# OBDII-Ist.net
KiCad netlist of a schematic drawn in Altium Designer
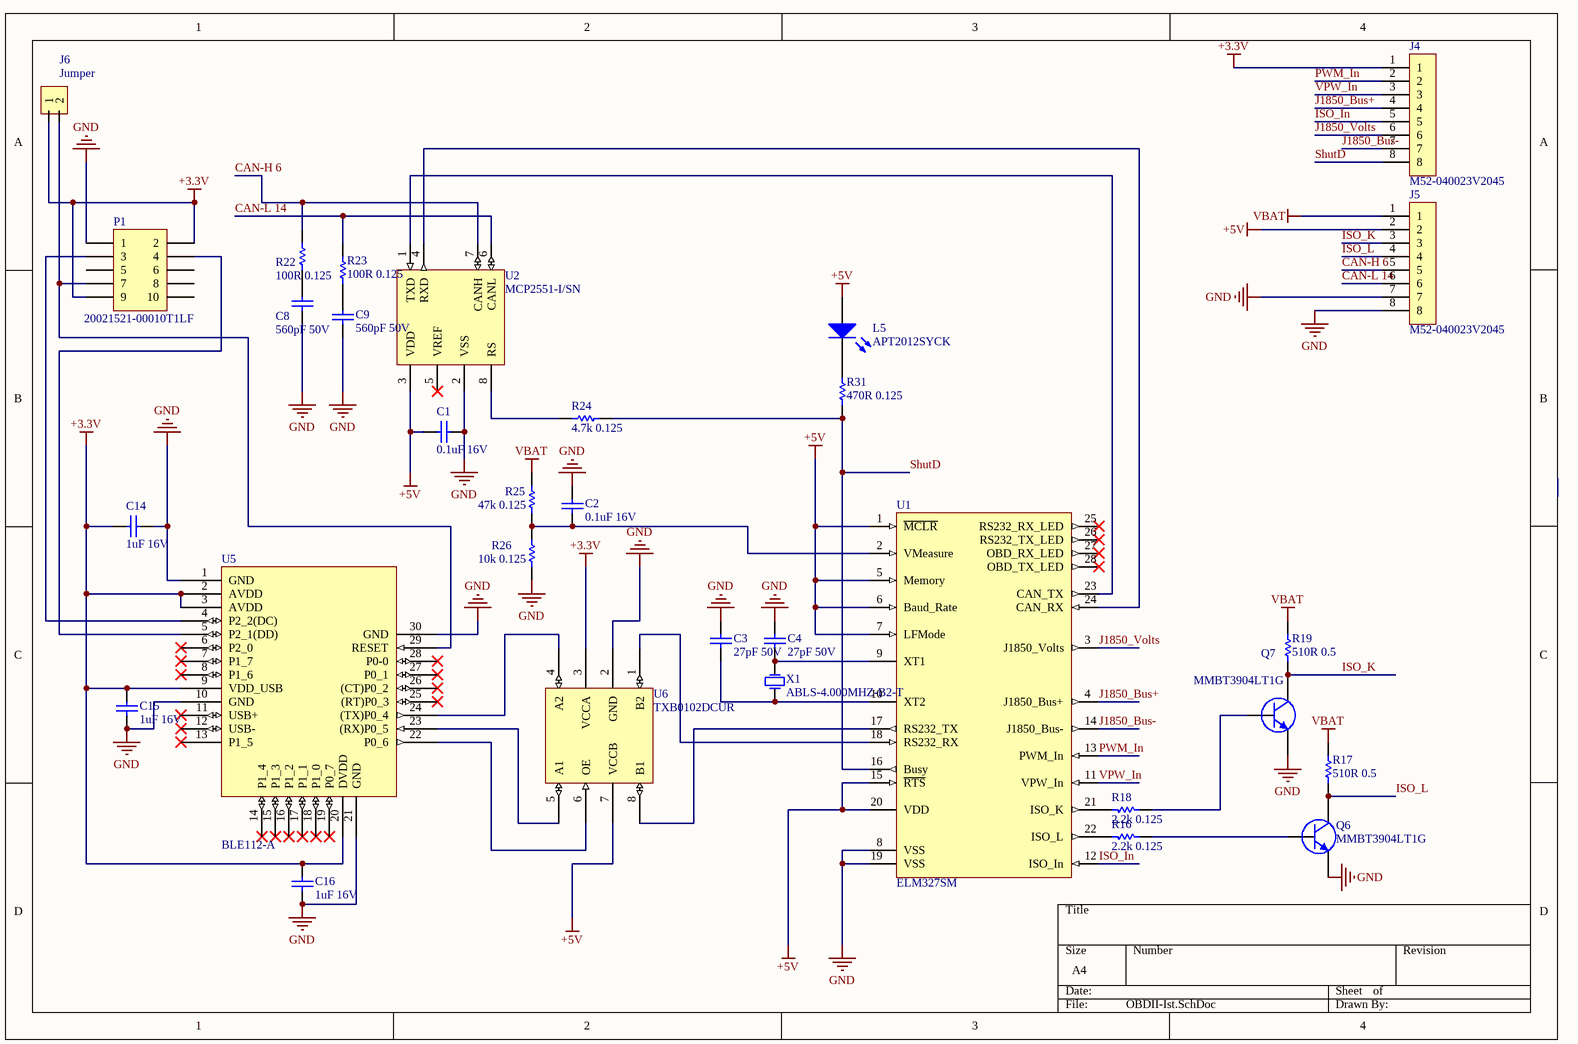
[diagram p0: OBDII-Ist.SchDoc]

(export (version "E")
  (design (tool "Eeschema 10.0.6"))
  (components
    (comp (ref "C1")
      (value "0.1uF 16V")
      (footprint "1608[0603]")
      (description "Surface-Mount Ceramic Multilayer Capacitor, 0.1uF, X5R, 10% Tolerance, 0603 Size, 16V")
      (fields (field (name "PUBLISHER") "Altium Limited"))
      (libsource (lib "OBDII-components") (part "GRM188R61C104KA01D"))
    )
    (comp (ref "C2")
      (value "0.1uF 16V")
      (footprint "1608[0603]")
      (description "Surface-Mount Ceramic Multilayer Capacitor, 0.1uF, X5R, 10% Tolerance, 0603 Size, 16V")
      (fields (field (name "PUBLISHER") "Altium Limited"))
      (libsource (lib "OBDII-components") (part "GRM188R61C104KA01D"))
    )
    (comp (ref "C3")
      (value "27pF 50V")
      (footprint "1608[0603]")
      (description "Surface-Mount Ceramic Multilayer Capacitor, 27pF, 5% Tolerance, 0603 Size, 50V")
      (fields (field (name "PUBLISHER") "Altium Limited"))
      (libsource (lib "OBDII-components") (part "CC0603JRNPO9BN270"))
    )
    (comp (ref "C4")
      (value "27pF 50V")
      (footprint "1608[0603]")
      (description "Surface-Mount Ceramic Multilayer Capacitor, 27pF, 5% Tolerance, 0603 Size, 50V")
      (fields (field (name "PUBLISHER") "Altium Limited"))
      (libsource (lib "OBDII-components") (part "CC0603JRNPO9BN270"))
    )
    (comp (ref "C8")
      (value "560pF 50V")
      (footprint "0402")
      (description "Surface-Mount Ceramic Multilayer Capacitor, 560pF, 5% Tolerance, 0402 Size, 50V")
      (fields (field (name "PUBLISHER") "Altium Limited"))
      (libsource (lib "OBDII-components") (part "C0402C561J5GACTU"))
    )
    (comp (ref "C9")
      (value "560pF 50V")
      (footprint "0402")
      (description "Surface-Mount Ceramic Multilayer Capacitor, 560pF, 5% Tolerance, 0402 Size, 50V")
      (fields (field (name "PUBLISHER") "Altium Limited"))
      (libsource (lib "OBDII-components") (part "C0402C561J5GACTU"))
    )
    (comp (ref "C14")
      (value "1uF 16V")
      (footprint "1608[0603]")
      (description "Surface-Mount Ceramic Multilayer Capacitor, 1uF, X7R, 10% Tolerance, 0603 Size, 16V")
      (libsource (lib "OBDII-components") (part "C1608X7R1C105K080AC"))
    )
    (comp (ref "C15")
      (value "1uF 16V")
      (footprint "1608[0603]")
      (description "Surface-Mount Ceramic Multilayer Capacitor, 1uF, X7R, 10% Tolerance, 0603 Size, 16V")
      (libsource (lib "OBDII-components") (part "C1608X7R1C105K080AC"))
    )
    (comp (ref "C16")
      (value "1uF 16V")
      (footprint "1608[0603]")
      (description "Surface-Mount Ceramic Multilayer Capacitor, 1uF, X7R, 10% Tolerance, 0603 Size, 16V")
      (libsource (lib "OBDII-components") (part "C1608X7R1C105K080AC"))
    )
    (comp (ref "J4")
      (value "M52-040023V2045")
      (footprint "M52-040023V2045_hols")
      (description "CONN HEADER .050\" 8POS PCB GOLD")
      (fields (field (name "MANUFACTURER") "Harwin"))
      (libsource (lib "OBDII-components") (part "M52-040023V2045_hols"))
    )
    (comp (ref "J5")
      (value "M52-040023V2045")
      (footprint "M52-040023V2045_hols")
      (description "CONN HEADER .050\" 8POS PCB GOLD")
      (fields (field (name "MANUFACTURER") "Harwin"))
      (libsource (lib "OBDII-components") (part "M52-040023V2045_hols"))
    )
    (comp (ref "J6")
      (value "Jumper")
      (footprint "Jumper")
      (description "Solder Jumper")
      (libsource (lib "OBDII-components") (part "Jumper"))
    )
    (comp (ref "L5")
      (value "APT2012SYCK")
      (footprint "LED-0805")
      (description "Typical BLUE SiC LED")
      (libsource (lib "OBDII-components") (part "APT2012SYCK"))
    )
    (comp (ref "P1")
      (value "20021521-00010T1LF")
      (footprint "20021521-00010T1LF")
      (description "Header, 5-Pin, Dual row,SMT SHOULDED")
      (fields (field (name "TYPE") "20021521-00010T1LF") (field (name "PUBLISHER") "Altium Limited"))
      (libsource (lib "OBDII-components") (part "20021521-00010T1LF"))
    )
    (comp (ref "Q6")
      (value "MMBT3904LT1G")
      (footprint "SOT23")
      (description "NPN 3904 General Purpose Amplifier")
      (fields
        (field (name "MANUFACTURER") "ON Semiconductor")
        (field (name "PUBLISHER") "Vanteon")
        (field (name "APPROVED") "Yes by Implemenation")
      )
      (libsource (lib "OBDII-components") (part "MMBT3904LT1G"))
    )
    (comp (ref "Q7")
      (value "MMBT3904LT1G")
      (footprint "SOT23")
      (description "NPN 3904 General Purpose Amplifier")
      (fields
        (field (name "MANUFACTURER") "ON Semiconductor")
        (field (name "PUBLISHER") "Vanteon")
        (field (name "APPROVED") "Yes by Implemenation")
      )
      (libsource (lib "OBDII-components") (part "MMBT3904LT1G"))
    )
    (comp (ref "R16")
      (value "2.2k 0.125")
      (footprint "ERA-0805")
      (description "Rectangular Thick Film Chip Resistor, 2.2 kOhm, 0.1% Tolerance, 0805 Size, 0.125 W")
      (libsource (lib "OBDII-components") (part "ERA-6AEB222V"))
    )
    (comp (ref "R17")
      (value "510R 0.5")
      (footprint "ERJ-1210")
      (description "Rectangular Thick Film Chip Resistor, 510 Ohm, 1% Tolerance, 1210 Size, 0.5 W")
      (libsource (lib "OBDII-components") (part "ERJ-14NF5100U"))
    )
    (comp (ref "R18")
      (value "2.2k 0.125")
      (footprint "ERA-0805")
      (description "Rectangular Thick Film Chip Resistor, 2.2 kOhm, 0.1% Tolerance, 0805 Size, 0.125 W")
      (libsource (lib "OBDII-components") (part "ERA-6AEB222V"))
    )
    (comp (ref "R19")
      (value "510R 0.5")
      (footprint "ERJ-1210")
      (description "Rectangular Thick Film Chip Resistor, 510 Ohm, 1% Tolerance, 1210 Size, 0.5 W")
      (libsource (lib "OBDII-components") (part "ERJ-14NF5100U"))
    )
    (comp (ref "R22")
      (value "100R 0.125")
      (footprint "ERA-0805")
      (description "Rectangular Thick Film Chip Resistor, 100 Ohm, 0.1% Tolerance, 0805 Size, 0.125 W")
      (libsource (lib "OBDII-components") (part "ERA-6AEB101V"))
    )
    (comp (ref "R23")
      (value "100R 0.125")
      (footprint "ERA-0805")
      (description "Rectangular Thick Film Chip Resistor, 100 Ohm, 0.1% Tolerance, 0805 Size, 0.125 W")
      (libsource (lib "OBDII-components") (part "ERA-6AEB101V"))
    )
    (comp (ref "R24")
      (value "4.7k 0.125")
      (footprint "ERA-0805")
      (description "Rectangular Thick Film Chip Resistor, 4.7 kOhm, 0.1% Tolerance, 0805 Size, 0.125 W")
      (libsource (lib "OBDII-components") (part "ERA-6AEB472V"))
    )
    (comp (ref "R25")
      (value "47k 0.125")
      (footprint "ERA-0805")
      (description "Rectangular Thick Film Chip Resistor, 47 kOhm, 0.1% Tolerance, 0805 Size, 0.125 W")
      (libsource (lib "OBDII-components") (part "ERA-6AEB473V"))
    )
    (comp (ref "R26")
      (value "10k 0.125")
      (footprint "ERA-0805")
      (description "Rectangular Thick Film Chip Resistor, 10 kOhm, 0.1% Tolerance, 0805 Size, 0.125 W")
      (libsource (lib "OBDII-components") (part "ERA-6AEB103V"))
    )
    (comp (ref "R31")
      (value "470R 0.125")
      (footprint "ERA-0805")
      (description "Rectangular Thick Film Chip Resistor, 470 Ohm, 0.1% Tolerance, 0805 Size, 0.125 W")
      (libsource (lib "OBDII-components") (part "ERA-6AEB471V"))
    )
    (comp (ref "U1")
      (value "ELM327SM")
      (footprint "SOIC-28N")
      (description "OBDII Interpreter IC")
      (fields (field (name "MANUFACTURER") "Elm Electronics"))
      (libsource (lib "OBDII-components") (part "ELM327_SOIC"))
    )
    (comp (ref "U2")
      (value "MCP2551-I/SN")
      (footprint "SOIC8N")
      (description "IC TRANSCEIVER CAN HI-SPD 8-SOIC")
      (fields (field (name "MANUFACTURER") "Microchip Technology"))
      (libsource (lib "OBDII-components") (part "MCP2551-I/SN"))
    )
    (comp (ref "U5")
      (value "BLE112-A")
      (footprint "BLE112-A - II")
      (description "BLE112 Bluetooth Smart Module")
      (libsource (lib "OBDII-components") (part "BLE112-A"))
    )
    (comp (ref "U6")
      (value "TXB0102DCUR")
      (footprint "TXB0102DCUR")
      (description "2-Bit Bidirectional Voltage-Level Translator with Auto Direction Sensing and +/-15-kV ESD Protect")
      (libsource (lib "OBDII-components") (part "TXB0102DCUR"))
    )
    (comp (ref "X1")
      (value "ABLS-4.000MHZ-B2-T")
      (footprint "HC-49/US")
      (description "CRYSTAL 4.000 MHZ 18PF SMD")
      (fields (field (name "MANUFACTURER") "Abracon"))
      (libsource (lib "OBDII-components") (part "ABLS-4.000MHZ-B2-T"))
    )
  )
  (nets
    (net (code "1") (name "+3.3V") (class "Default")
      (node (ref "C14") (pin "1") (pinfunction "1_1") (pintype "passive"))
      (node (ref "C15") (pin "2") (pinfunction "2_2") (pintype "passive"))
      (node (ref "C16") (pin "2") (pinfunction "2_2") (pintype "passive"))
      (node (ref "J4") (pin "1") (pinfunction "1_1") (pintype "passive"))
      (node (ref "J6") (pin "1") (pinfunction "1_1") (pintype "passive"))
      (node (ref "P1") (pin "2") (pinfunction "2_2") (pintype "passive"))
      (node (ref "P1") (pin "9") (pinfunction "9_9") (pintype "passive"))
      (node (ref "U5") (pin "2") (pinfunction "AVDD_2") (pintype "power_in"))
      (node (ref "U5") (pin "20") (pinfunction "DVDD_20") (pintype "power_in"))
      (node (ref "U5") (pin "3") (pinfunction "AVDD_3") (pintype "power_in"))
      (node (ref "U5") (pin "9") (pinfunction "VDD_USB_9") (pintype "power_in"))
      (node (ref "U6") (pin "3") (pinfunction "VCCA_3") (pintype "power_in"))
    )
    (net (code "2") (name "+5V") (class "Default")
      (node (ref "C1") (pin "1") (pinfunction "1_1") (pintype "passive"))
      (node (ref "J5") (pin "2") (pinfunction "2_2") (pintype "passive"))
      (node (ref "L5") (pin "1") (pinfunction "A_1") (pintype "passive"))
      (node (ref "U1") (pin "1") (pinfunction "~{MCLR}_1") (pintype "input"))
      (node (ref "U1") (pin "15") (pinfunction "~{RTS}_15") (pintype "input"))
      (node (ref "U1") (pin "20") (pinfunction "VDD_20") (pintype "power_in"))
      (node (ref "U1") (pin "5") (pinfunction "Memory_5") (pintype "input"))
      (node (ref "U1") (pin "6") (pinfunction "Baud_Rate_6") (pintype "input"))
      (node (ref "U1") (pin "7") (pinfunction "LFMode_7") (pintype "input"))
      (node (ref "U2") (pin "3") (pinfunction "VDD_3") (pintype "power_in"))
      (node (ref "U6") (pin "7") (pinfunction "VCCB_7") (pintype "power_in"))
    )
    (net (code "3") (name "/CAN-H 6") (class "Default")
      (node (ref "J5") (pin "5") (pinfunction "5_5") (pintype "passive"))
      (node (ref "R22") (pin "2") (pinfunction "2_2") (pintype "passive"))
      (node (ref "U2") (pin "7") (pinfunction "CANH_7") (pintype "bidirectional"))
    )
    (net (code "4") (name "/CAN-L 14") (class "Default")
      (node (ref "J5") (pin "6") (pinfunction "6_6") (pintype "passive"))
      (node (ref "R23") (pin "2") (pinfunction "2_2") (pintype "passive"))
      (node (ref "U2") (pin "6") (pinfunction "CANL_6") (pintype "bidirectional"))
    )
    (net (code "5") (name "/ISO_In") (class "Default")
      (node (ref "J4") (pin "5") (pinfunction "5_5") (pintype "passive"))
      (node (ref "U1") (pin "12") (pinfunction "ISO_In_12") (pintype "input"))
    )
    (net (code "6") (name "/ISO_K") (class "Default")
      (node (ref "J5") (pin "3") (pinfunction "3_3") (pintype "passive"))
      (node (ref "Q7") (pin "3") (pinfunction "C_3") (pintype "passive"))
      (node (ref "R19") (pin "1") (pinfunction "1_1") (pintype "passive"))
    )
    (net (code "7") (name "/ISO_L") (class "Default")
      (node (ref "J5") (pin "4") (pinfunction "4_4") (pintype "passive"))
      (node (ref "Q6") (pin "3") (pinfunction "C_3") (pintype "passive"))
      (node (ref "R17") (pin "1") (pinfunction "1_1") (pintype "passive"))
    )
    (net (code "8") (name "/J1850_Bus+") (class "Default")
      (node (ref "J4") (pin "4") (pinfunction "4_4") (pintype "passive"))
      (node (ref "U1") (pin "4") (pinfunction "J1850_Bus+_4") (pintype "output"))
    )
    (net (code "9") (name "/J1850_Bus-") (class "Default")
      (node (ref "J4") (pin "7") (pinfunction "7_7") (pintype "passive"))
      (node (ref "U1") (pin "14") (pinfunction "J1850_Bus-_14") (pintype "output"))
    )
    (net (code "10") (name "/J1850_Volts") (class "Default")
      (node (ref "J4") (pin "6") (pinfunction "6_6") (pintype "passive"))
      (node (ref "U1") (pin "3") (pinfunction "J1850_Volts_3") (pintype "output"))
    )
    (net (code "11") (name "/PWM_In") (class "Default")
      (node (ref "J4") (pin "2") (pinfunction "2_2") (pintype "passive"))
      (node (ref "U1") (pin "13") (pinfunction "PWM_In_13") (pintype "input"))
    )
    (net (code "12") (name "/ShutD") (class "Default")
      (node (ref "J4") (pin "8") (pinfunction "8_8") (pintype "passive"))
      (node (ref "R24") (pin "2") (pinfunction "2_2") (pintype "passive"))
      (node (ref "R31") (pin "1") (pinfunction "1_1") (pintype "passive"))
      (node (ref "U1") (pin "16") (pinfunction "Busy_16") (pintype "output"))
    )
    (net (code "13") (name "/VPW_In") (class "Default")
      (node (ref "J4") (pin "3") (pinfunction "3_3") (pintype "passive"))
      (node (ref "U1") (pin "11") (pinfunction "VPW_In_11") (pintype "input"))
    )
    (net (code "14") (name "GND") (class "Default")
      (node (ref "C1") (pin "2") (pinfunction "2_2") (pintype "passive"))
      (node (ref "C14") (pin "2") (pinfunction "2_2") (pintype "passive"))
      (node (ref "C15") (pin "1") (pinfunction "1_1") (pintype "passive"))
      (node (ref "C16") (pin "1") (pinfunction "1_1") (pintype "passive"))
      (node (ref "C2") (pin "2") (pinfunction "2_2") (pintype "passive"))
      (node (ref "C3") (pin "2") (pinfunction "2_2") (pintype "passive"))
      (node (ref "C4") (pin "2") (pinfunction "2_2") (pintype "passive"))
      (node (ref "C8") (pin "1") (pinfunction "1_1") (pintype "passive"))
      (node (ref "C9") (pin "1") (pinfunction "1_1") (pintype "passive"))
      (node (ref "J5") (pin "7") (pinfunction "7_7") (pintype "passive"))
      (node (ref "J5") (pin "8") (pinfunction "8_8") (pintype "passive"))
      (node (ref "P1") (pin "1") (pinfunction "1_1") (pintype "passive"))
      (node (ref "Q6") (pin "2") (pinfunction "E_2") (pintype "passive"))
      (node (ref "Q7") (pin "2") (pinfunction "E_2") (pintype "passive"))
      (node (ref "R26") (pin "1") (pinfunction "1_1") (pintype "passive"))
      (node (ref "U1") (pin "19") (pinfunction "VSS_19") (pintype "power_in"))
      (node (ref "U1") (pin "8") (pinfunction "VSS_8") (pintype "power_in"))
      (node (ref "U2") (pin "2") (pinfunction "VSS_2") (pintype "power_in"))
      (node (ref "U5") (pin "1") (pinfunction "GND_1") (pintype "power_in"))
      (node (ref "U5") (pin "10") (pinfunction "GND_10") (pintype "passive"))
      (node (ref "U5") (pin "21") (pinfunction "GND_21") (pintype "power_in"))
      (node (ref "U5") (pin "30") (pinfunction "GND_30") (pintype "power_in"))
      (node (ref "U6") (pin "2") (pinfunction "GND_2") (pintype "power_in"))
    )
    (net (code "15") (name "Net-(C8-Pad2)") (class "Default")
      (node (ref "C8") (pin "2") (pinfunction "2_2") (pintype "passive"))
      (node (ref "R22") (pin "1") (pinfunction "1_1") (pintype "passive"))
    )
    (net (code "16") (name "Net-(C9-Pad2)") (class "Default")
      (node (ref "C9") (pin "2") (pinfunction "2_2") (pintype "passive"))
      (node (ref "R23") (pin "1") (pinfunction "1_1") (pintype "passive"))
    )
    (net (code "17") (name "Net-(L5-K)") (class "Default")
      (node (ref "L5") (pin "2") (pinfunction "K_2") (pintype "passive"))
      (node (ref "R31") (pin "2") (pinfunction "2_2") (pintype "passive"))
    )
    (net (code "18") (name "Net-(Q6-B)") (class "Default")
      (node (ref "Q6") (pin "1") (pinfunction "B_1") (pintype "passive"))
      (node (ref "R16") (pin "1") (pinfunction "1_1") (pintype "passive"))
    )
    (net (code "19") (name "Net-(Q7-B)") (class "Default")
      (node (ref "Q7") (pin "1") (pinfunction "B_1") (pintype "passive"))
      (node (ref "R18") (pin "1") (pinfunction "1_1") (pintype "passive"))
    )
    (net (code "20") (name "Net-(U1-CAN_RX)") (class "Default")
      (node (ref "U1") (pin "24") (pinfunction "CAN_RX_24") (pintype "input"))
      (node (ref "U2") (pin "4") (pinfunction "RXD_4") (pintype "output"))
    )
    (net (code "21") (name "Net-(U1-CAN_TX)") (class "Default")
      (node (ref "U1") (pin "23") (pinfunction "CAN_TX_23") (pintype "output"))
      (node (ref "U2") (pin "1") (pinfunction "TXD_1") (pintype "input"))
    )
    (net (code "22") (name "Net-(U1-ISO_K)") (class "Default")
      (node (ref "R18") (pin "2") (pinfunction "2_2") (pintype "passive"))
      (node (ref "U1") (pin "21") (pinfunction "ISO_K_21") (pintype "output"))
    )
    (net (code "23") (name "Net-(U1-ISO_L)") (class "Default")
      (node (ref "R16") (pin "2") (pinfunction "2_2") (pintype "passive"))
      (node (ref "U1") (pin "22") (pinfunction "ISO_L_22") (pintype "output"))
    )
    (net (code "24") (name "Net-(U1-RS232_RX)") (class "Default")
      (node (ref "U1") (pin "18") (pinfunction "RS232_RX_18") (pintype "input"))
      (node (ref "U6") (pin "1") (pinfunction "B2_1") (pintype "bidirectional"))
    )
    (net (code "25") (name "Net-(U1-RS232_TX)") (class "Default")
      (node (ref "U1") (pin "17") (pinfunction "RS232_TX_17") (pintype "output"))
      (node (ref "U6") (pin "8") (pinfunction "B1_8") (pintype "bidirectional"))
    )
    (net (code "26") (name "Net-(U1-VMeasure)") (class "Default")
      (node (ref "C2") (pin "1") (pinfunction "1_1") (pintype "passive"))
      (node (ref "R25") (pin "1") (pinfunction "1_1") (pintype "passive"))
      (node (ref "R26") (pin "2") (pinfunction "2_2") (pintype "passive"))
      (node (ref "U1") (pin "2") (pinfunction "VMeasure_2") (pintype "input"))
    )
    (net (code "27") (name "Net-(U1-XT1)") (class "Default")
      (node (ref "C4") (pin "1") (pinfunction "1_1") (pintype "passive"))
      (node (ref "U1") (pin "9") (pinfunction "XT1_9") (pintype "passive"))
      (node (ref "X1") (pin "2") (pinfunction "OSC2_2") (pintype "passive"))
    )
    (net (code "28") (name "Net-(U1-XT2)") (class "Default")
      (node (ref "C3") (pin "1") (pinfunction "1_1") (pintype "passive"))
      (node (ref "U1") (pin "10") (pinfunction "XT2_10") (pintype "passive"))
      (node (ref "X1") (pin "1") (pinfunction "OSC1_1") (pintype "passive"))
    )
    (net (code "29") (name "Net-(U2-RS)") (class "Default")
      (node (ref "R24") (pin "1") (pinfunction "1_1") (pintype "passive"))
      (node (ref "U2") (pin "8") (pinfunction "RS_8") (pintype "passive"))
    )
    (net (code "30") (name "Net-(U5-(RX)P0_5)") (class "Default")
      (node (ref "U5") (pin "23") (pinfunction "(RX)P0_5_23") (pintype "input"))
      (node (ref "U6") (pin "5") (pinfunction "A1_5") (pintype "bidirectional"))
    )
    (net (code "31") (name "Net-(U5-(TX)P0_4)") (class "Default")
      (node (ref "U5") (pin "24") (pinfunction "(TX)P0_4_24") (pintype "output"))
      (node (ref "U6") (pin "4") (pinfunction "A2_4") (pintype "bidirectional"))
    )
    (net (code "32") (name "Net-(U5-P0_6)") (class "Default")
      (node (ref "U5") (pin "22") (pinfunction "P0_6_22") (pintype "output"))
      (node (ref "U6") (pin "6") (pinfunction "OE_6") (pintype "input"))
    )
    (net (code "33") (name "Net-(U5-P2_1(DD))") (class "Default")
      (node (ref "P1") (pin "4") (pinfunction "4_4") (pintype "passive"))
      (node (ref "U5") (pin "5") (pinfunction "P2_1(DD)_5") (pintype "bidirectional"))
    )
    (net (code "34") (name "Net-(U5-P2_2(DC))") (class "Default")
      (node (ref "P1") (pin "3") (pinfunction "3_3") (pintype "passive"))
      (node (ref "U5") (pin "4") (pinfunction "P2_2(DC)_4") (pintype "bidirectional"))
    )
    (net (code "35") (name "Net-(U5-RESET)") (class "Default")
      (node (ref "J6") (pin "2") (pinfunction "2_2") (pintype "passive"))
      (node (ref "P1") (pin "7") (pinfunction "7_7") (pintype "passive"))
      (node (ref "U5") (pin "29") (pinfunction "RESET_29") (pintype "input"))
    )
    (net (code "36") (name "VBAT") (class "Default")
      (node (ref "J5") (pin "1") (pinfunction "1_1") (pintype "passive"))
      (node (ref "R17") (pin "2") (pinfunction "2_2") (pintype "passive"))
      (node (ref "R19") (pin "2") (pinfunction "2_2") (pintype "passive"))
      (node (ref "R25") (pin "2") (pinfunction "2_2") (pintype "passive"))
    )
    (net (code "37") (name "unconnected-(P1-Pad5)") (class "Default")
      (node (ref "P1") (pin "5") (pinfunction "5_5") (pintype "passive"))
    )
    (net (code "38") (name "unconnected-(P1-Pad6)") (class "Default")
      (node (ref "P1") (pin "6") (pinfunction "6_6") (pintype "passive"))
    )
    (net (code "39") (name "unconnected-(P1-Pad8)") (class "Default")
      (node (ref "P1") (pin "8") (pinfunction "8_8") (pintype "passive"))
    )
    (net (code "40") (name "unconnected-(P1-Pad10)") (class "Default")
      (node (ref "P1") (pin "10") (pinfunction "10_10") (pintype "passive"))
    )
    (net (code "41") (name "unconnected-(U1-OBD_RX_LED-Pad27)") (class "Default")
      (node (ref "U1") (pin "27") (pinfunction "OBD_RX_LED_27") (pintype "output+no_connect"))
    )
    (net (code "42") (name "unconnected-(U1-OBD_TX_LED-Pad28)") (class "Default")
      (node (ref "U1") (pin "28") (pinfunction "OBD_TX_LED_28") (pintype "output+no_connect"))
    )
    (net (code "43") (name "unconnected-(U1-RS232_RX_LED-Pad25)") (class "Default")
      (node (ref "U1") (pin "25") (pinfunction "RS232_RX_LED_25") (pintype "output+no_connect"))
    )
    (net (code "44") (name "unconnected-(U1-RS232_TX_LED-Pad26)") (class "Default")
      (node (ref "U1") (pin "26") (pinfunction "RS232_TX_LED_26") (pintype "output+no_connect"))
    )
    (net (code "45") (name "unconnected-(U2-VREF-Pad5)") (class "Default")
      (node (ref "U2") (pin "5") (pinfunction "VREF_5") (pintype "passive+no_connect"))
    )
    (net (code "46") (name "unconnected-(U5-(CT)P0_2-Pad26)") (class "Default")
      (node (ref "U5") (pin "26") (pinfunction "(CT)P0_2_26") (pintype "bidirectional+no_connect"))
    )
    (net (code "47") (name "unconnected-(U5-(RT)P0_3-Pad25)") (class "Default")
      (node (ref "U5") (pin "25") (pinfunction "(RT)P0_3_25") (pintype "bidirectional+no_connect"))
    )
    (net (code "48") (name "unconnected-(U5-P0-0-Pad28)") (class "Default")
      (node (ref "U5") (pin "28") (pinfunction "P0-0_28") (pintype "bidirectional+no_connect"))
    )
    (net (code "49") (name "unconnected-(U5-P0_1-Pad27)") (class "Default")
      (node (ref "U5") (pin "27") (pinfunction "P0_1_27") (pintype "bidirectional+no_connect"))
    )
    (net (code "50") (name "unconnected-(U5-P0_7-Pad19)") (class "Default")
      (node (ref "U5") (pin "19") (pinfunction "P0_7_19") (pintype "bidirectional+no_connect"))
    )
    (net (code "51") (name "unconnected-(U5-P1_0-Pad18)") (class "Default")
      (node (ref "U5") (pin "18") (pinfunction "P1_0_18") (pintype "bidirectional+no_connect"))
    )
    (net (code "52") (name "unconnected-(U5-P1_1-Pad17)") (class "Default")
      (node (ref "U5") (pin "17") (pinfunction "P1_1_17") (pintype "bidirectional+no_connect"))
    )
    (net (code "53") (name "unconnected-(U5-P1_2-Pad16)") (class "Default")
      (node (ref "U5") (pin "16") (pinfunction "P1_2_16") (pintype "bidirectional+no_connect"))
    )
    (net (code "54") (name "unconnected-(U5-P1_3-Pad15)") (class "Default")
      (node (ref "U5") (pin "15") (pinfunction "P1_3_15") (pintype "bidirectional+no_connect"))
    )
    (net (code "55") (name "unconnected-(U5-P1_4-Pad14)") (class "Default")
      (node (ref "U5") (pin "14") (pinfunction "P1_4_14") (pintype "bidirectional+no_connect"))
    )
    (net (code "56") (name "unconnected-(U5-P1_5-Pad13)") (class "Default")
      (node (ref "U5") (pin "13") (pinfunction "P1_5_13") (pintype "passive+no_connect"))
    )
    (net (code "57") (name "unconnected-(U5-P1_6-Pad8)") (class "Default")
      (node (ref "U5") (pin "8") (pinfunction "P1_6_8") (pintype "bidirectional+no_connect"))
    )
    (net (code "58") (name "unconnected-(U5-P1_7-Pad7)") (class "Default")
      (node (ref "U5") (pin "7") (pinfunction "P1_7_7") (pintype "bidirectional+no_connect"))
    )
    (net (code "59") (name "unconnected-(U5-P2_0-Pad6)") (class "Default")
      (node (ref "U5") (pin "6") (pinfunction "P2_0_6") (pintype "bidirectional+no_connect"))
    )
    (net (code "60") (name "unconnected-(U5-USB+-Pad11)") (class "Default")
      (node (ref "U5") (pin "11") (pinfunction "USB+_11") (pintype "bidirectional+no_connect"))
    )
    (net (code "61") (name "unconnected-(U5-USB--Pad12)") (class "Default")
      (node (ref "U5") (pin "12") (pinfunction "USB-_12") (pintype "bidirectional+no_connect"))
    )
  )
)
